# SPI_IFC.net
KiCad netlist of a schematic drawn in Altium Designer
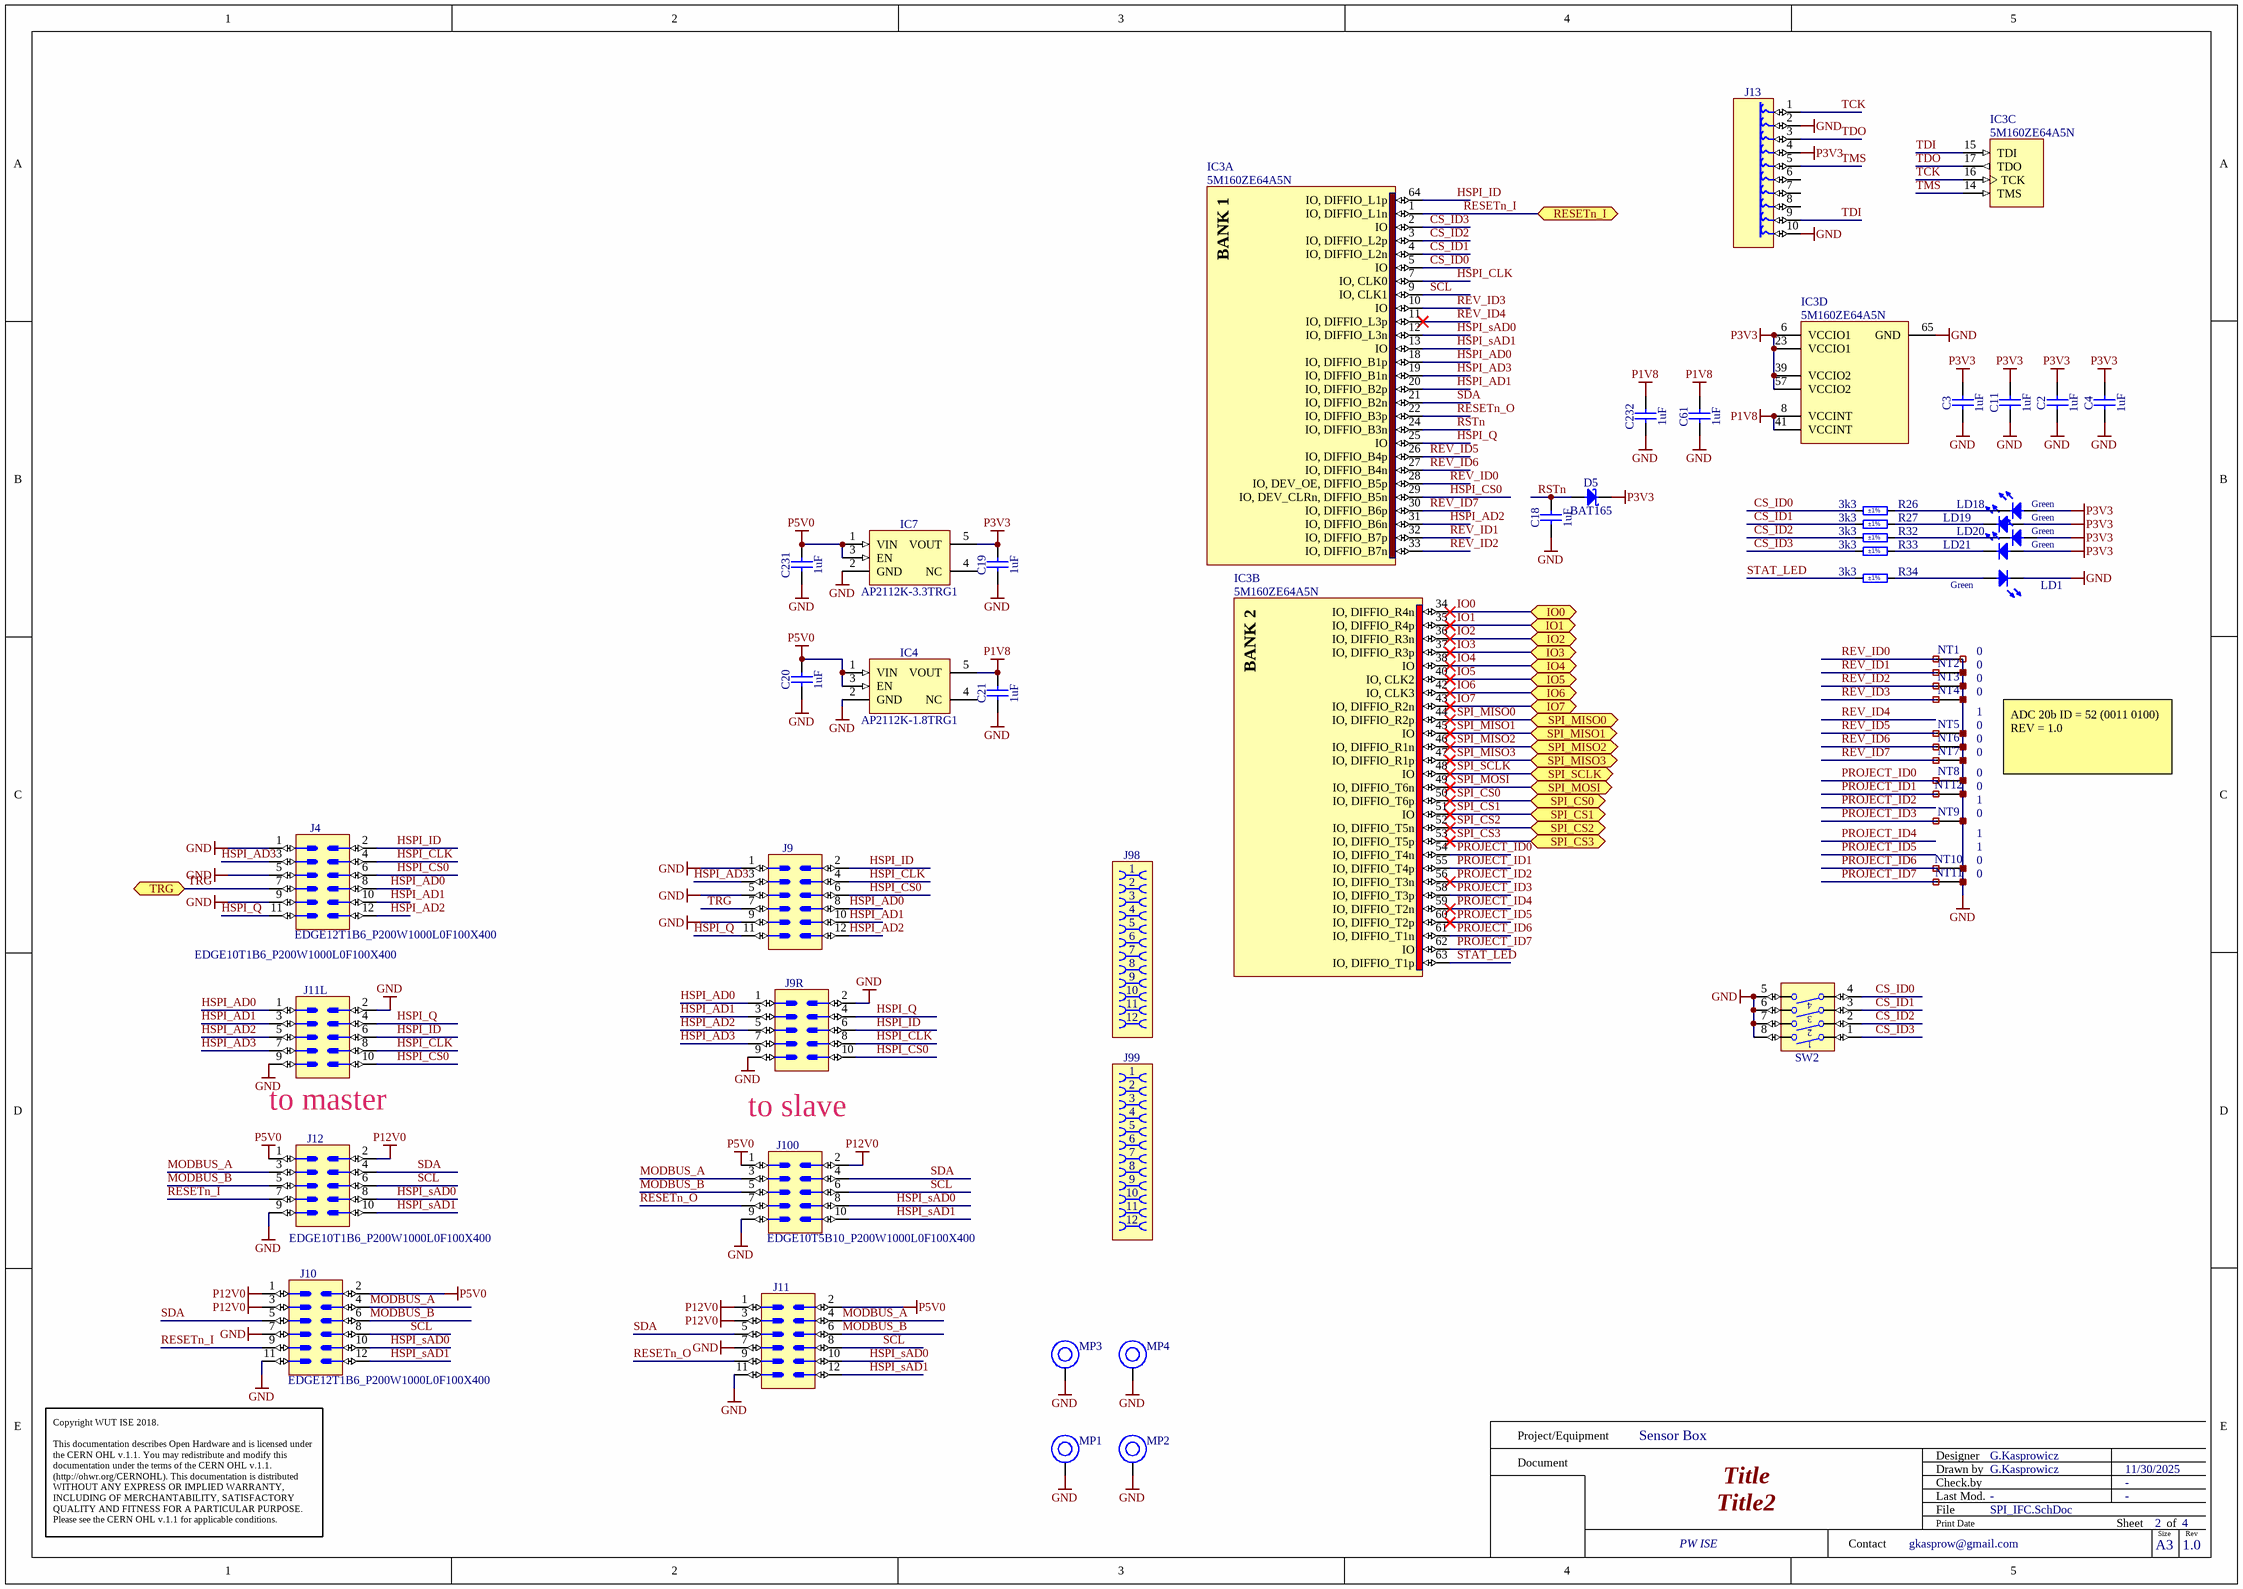
[diagram p0: SPI_IFC.SchDoc]

(export (version "E")
  (design (tool "Eeschema 10.0.6"))
  (components
    (comp (ref "C2")
      (value "1uF")
      (footprint "CAPC1005X55N")
      (description "Non-polarised capacitor")
      (fields
        (field (name "PART NUMBER") "CC0402_1UF_16V_10%_X5R")
        (field (name "VOLTAGE") "16V")
        (field (name "AUTHOR") "CERN DEM JLC")
      )
      (libsource (lib "Capacitors") (part "Capacitor - non polarized"))
    )
    (comp (ref "C3")
      (value "1uF")
      (footprint "CAPC1005X55N")
      (description "Non-polarised capacitor")
      (fields
        (field (name "PART NUMBER") "CC0402_1UF_16V_10%_X5R")
        (field (name "VOLTAGE") "16V")
        (field (name "AUTHOR") "CERN DEM JLC")
      )
      (libsource (lib "Capacitors") (part "Capacitor - non polarized"))
    )
    (comp (ref "C4")
      (value "1uF")
      (footprint "CAPC1005X55N")
      (description "Non-polarised capacitor")
      (fields
        (field (name "PART NUMBER") "CC0402_1UF_16V_10%_X5R")
        (field (name "VOLTAGE") "16V")
        (field (name "AUTHOR") "CERN DEM JLC")
      )
      (libsource (lib "Capacitors") (part "Capacitor - non polarized"))
    )
    (comp (ref "C11")
      (value "1uF")
      (footprint "CAPC1005X55N")
      (description "Non-polarised capacitor")
      (fields
        (field (name "PART NUMBER") "CC0402_1UF_16V_10%_X5R")
        (field (name "VOLTAGE") "16V")
        (field (name "AUTHOR") "CERN DEM JLC")
      )
      (libsource (lib "Capacitors") (part "Capacitor - non polarized"))
    )
    (comp (ref "C18")
      (value "1uF")
      (footprint "CAPC1005X55N")
      (description "Non-polarised capacitor")
      (fields
        (field (name "PART NUMBER") "CC0402_1UF_16V_10%_X5R")
        (field (name "VOLTAGE") "16V")
        (field (name "AUTHOR") "CERN DEM JLC")
      )
      (libsource (lib "Capacitors") (part "Capacitor - non polarized"))
    )
    (comp (ref "C19")
      (value "1uF")
      (footprint "CAPC1005X55N")
      (description "Non-polarised capacitor")
      (fields
        (field (name "PART NUMBER") "CC0402_1UF_16V_10%_X5R")
        (field (name "VOLTAGE") "16V")
        (field (name "AUTHOR") "CERN DEM JLC")
      )
      (libsource (lib "Capacitors") (part "Capacitor - non polarized"))
    )
    (comp (ref "C20")
      (value "1uF")
      (footprint "CAPC1005X55N")
      (description "Non-polarised capacitor")
      (fields
        (field (name "PART NUMBER") "CC0402_1UF_16V_10%_X5R")
        (field (name "VOLTAGE") "16V")
        (field (name "AUTHOR") "CERN DEM JLC")
      )
      (libsource (lib "Capacitors") (part "Capacitor - non polarized"))
    )
    (comp (ref "C21")
      (value "1uF")
      (footprint "CAPC1005X55N")
      (description "Non-polarised capacitor")
      (fields
        (field (name "PART NUMBER") "CC0402_1UF_16V_10%_X5R")
        (field (name "VOLTAGE") "16V")
        (field (name "AUTHOR") "CERN DEM JLC")
      )
      (libsource (lib "Capacitors") (part "Capacitor - non polarized"))
    )
    (comp (ref "C61")
      (value "1uF")
      (footprint "CAPC1005X55N")
      (description "Non-polarised capacitor")
      (fields
        (field (name "PART NUMBER") "CC0402_1UF_16V_10%_X5R")
        (field (name "VOLTAGE") "16V")
        (field (name "AUTHOR") "CERN DEM JLC")
      )
      (libsource (lib "Capacitors") (part "Capacitor - non polarized"))
    )
    (comp (ref "C231")
      (value "1uF")
      (footprint "CAPC1005X55N")
      (description "Non-polarised capacitor")
      (fields
        (field (name "PART NUMBER") "CC0402_1UF_16V_10%_X5R")
        (field (name "VOLTAGE") "16V")
        (field (name "AUTHOR") "CERN DEM JLC")
      )
      (libsource (lib "Capacitors") (part "Capacitor - non polarized"))
    )
    (comp (ref "C232")
      (value "1uF")
      (footprint "CAPC1005X55N")
      (description "Non-polarised capacitor")
      (fields
        (field (name "PART NUMBER") "CC0402_1UF_16V_10%_X5R")
        (field (name "VOLTAGE") "16V")
        (field (name "AUTHOR") "CERN DEM JLC")
      )
      (libsource (lib "Capacitors") (part "Capacitor - non polarized"))
    )
    (comp (ref "D5")
      (value "BAT165")
      (footprint "SOD2512X110N")
      (description "Schottky Diode")
      (fields
        (field (name "VOLTAGE") "40V")
        (field (name "POWER") "750mA")
        (field (name "AUTHOR") "CERN DEM JLC")
      )
      (libsource (lib "ICs And Semiconductors") (part "Diode Schottky"))
    )
    (comp (ref "IC3")
      (value "5M160ZE64A5N")
      (footprint "QFP40P900X900X120-65N-S550")
      (fields (field (name "MANUFACTURER") "ALTERA") (field (name "AUTHOR") "CERN DEM JLC"))
      (libsource (lib "ICs And Semiconductors") (part "5M160ZE64A5N"))
    )
    (comp (ref "IC4")
      (value "AP2112K-1.8TRG1")
      (footprint "SOT95P285X140-5N")
      (description "600mA CMOS Low Dropout Linear Regulator with Enable")
      (fields
        (field (name "MANUFACTURER") "DIODES INCORPORATED")
        (field (name "MANUFACTURER PART NUMBER") "AP2112K-1.8")
        (field (name "AUTHOR") "CERN DEM JLC")
      )
      (libsource (lib "ICs And Semiconductors") (part "AP2112K"))
    )
    (comp (ref "IC7")
      (value "AP2112K-3.3TRG1")
      (footprint "SOT95P285X140-5N")
      (description "600mA CMOS Low Dropout Linear Regulator with Enable")
      (fields
        (field (name "MANUFACTURER") "DIODES INCORPORATED")
        (field (name "MANUFACTURER PART NUMBER") "AP2112K-3.3")
        (field (name "AUTHOR") "CERN DEM MR")
      )
      (libsource (lib "ICs And Semiconductors") (part "AP2112K"))
    )
    (comp (ref "J4")
      (value "~")
      (footprint "EDGE12T1B6_P200W1000L0F100X400")
      (description "PCB Edge Connector 12 (2x6)")
      (fields
        (field (name "PART NUMBER") "EDGE10T1B6_P200W1000L0F100X400")
        (field (name "AUTHOR") "CERN DEM MR")
      )
      (libsource (lib "Connectors") (part "PCB Edge Connector 12 (2x6)"))
    )
    (comp (ref "J9")
      (value "~")
      (footprint "EDGE12T5B10_P200W1000L0F100X400")
      (description "PCB Edge Connector 12 (2x6)")
      (fields (field (name "PART NUMBER") "EDGE12T5B10_P200W1000L0F100X400") (field (name "AUTHOR") "GK"))
      (libsource (lib "Connectors") (part "PCB Edge Connector 12 (2x6) R"))
    )
    (comp (ref "J9R")
      (value "~")
      (footprint "EDGE10T5B10_P200W1000L0F100X400")
      (description "PCB Edge Connector 10 (2x5)")
      (fields
        (field (name "PART NUMBER") "EDGE10T5B10_P200W1000L0F100X400")
        (field (name "AUTHOR") "CERN DEM MR")
      )
      (libsource (lib "Connectors") (part "PCB Edge Connector 10 (2x5)"))
    )
    (comp (ref "J10")
      (value "~")
      (footprint "EDGE12T1B6_P200W1000L0F100X400")
      (description "PCB Edge Connector 12 (2x6)")
      (fields
        (field (name "PART NUMBER") "EDGE10T1B6_P200W1000L0F100X400")
        (field (name "AUTHOR") "CERN DEM MR")
      )
      (libsource (lib "Connectors") (part "PCB Edge Connector 12 (2x6)"))
    )
    (comp (ref "J11")
      (value "~")
      (footprint "EDGE12T5B10_P200W1000L0F100X400")
      (description "PCB Edge Connector 12 (2x6)")
      (fields (field (name "PART NUMBER") "EDGE12T5B10_P200W1000L0F100X400") (field (name "AUTHOR") "GK"))
      (libsource (lib "Connectors") (part "PCB Edge Connector 12 (2x6) R"))
    )
    (comp (ref "J11L")
      (value "~")
      (footprint "EDGE10T1B6_P200W1000L0F100X400")
      (description "PCB Edge Connector 10 (2x5)")
      (fields
        (field (name "PART NUMBER") "EDGE10T1B6_P200W1000L0F100X400")
        (field (name "AUTHOR") "CERN DEM MR")
      )
      (libsource (lib "Connectors") (part "PCB Edge Connector 10 (2x5)"))
    )
    (comp (ref "J12")
      (value "~")
      (footprint "EDGE10T1B6_P200W1000L0F100X400")
      (description "PCB Edge Connector 10 (2x5)")
      (fields
        (field (name "PART NUMBER") "EDGE10T1B6_P200W1000L0F100X400")
        (field (name "AUTHOR") "CERN DEM MR")
      )
      (libsource (lib "Connectors") (part "PCB Edge Connector 10 (2x5)"))
    )
    (comp (ref "J13")
      (value "TC2050-IDC")
      (footprint "TC2050-IDC")
      (description "TC2030-MCP and TC2050-IDC Pad Contact")
      (fields (field (name "AUTHOR") "CERN DEM HF"))
      (libsource (lib "Eletro-mechanical") (part "TC2050-IDC"))
    )
    (comp (ref "J98")
      (value "~")
      (footprint "AVX_009159012761916")
      (description "Open Ended Card Edge Connector, 9159 Series")
      (fields
        (field (name "PART NUMBER") "AVX_0009159012761916")
        (field (name "MANUFACTURER") "AVX")
        (field (name "AUTHOR") "GK")
      )
      (libsource (lib "Connectors") (part "AVX_009159012761916"))
    )
    (comp (ref "J99")
      (value "~")
      (footprint "AVX_009159012761916")
      (description "Open Ended Card Edge Connector, 9159 Series")
      (fields
        (field (name "PART NUMBER") "AVX_0009159012761916")
        (field (name "MANUFACTURER") "AVX")
        (field (name "AUTHOR") "GK")
      )
      (libsource (lib "Connectors") (part "AVX_009159012761916"))
    )
    (comp (ref "J100")
      (value "~")
      (footprint "EDGE10T5B10_P200W1000L0F100X400")
      (description "PCB Edge Connector 10 (2x5)")
      (fields
        (field (name "PART NUMBER") "EDGE10T5B10_P200W1000L0F100X400")
        (field (name "AUTHOR") "CERN DEM MR")
      )
      (libsource (lib "Connectors") (part "PCB Edge Connector 10 (2x5)"))
    )
    (comp (ref "LD1")
      (value "Green")
      (footprint "LED_KINGBRIGHT_KP-1608CGCK")
      (description "LED Green 1C 2A")
      (fields
        (field (name "PART NUMBER") "LED_KINGBRIGHT_KP-1608CGCK")
        (field (name "MANUFACTURER") "KINGBRIGHT")
        (field (name "AUTHOR") "CERN DEM HF")
      )
      (libsource (lib "ICs And Semiconductors") (part "LED Green 1C 2A"))
    )
    (comp (ref "LD18")
      (value "Green")
      (footprint "LED_KINGBRIGHT_KP-1608CGCK")
      (description "LED Green 1C 2A")
      (fields
        (field (name "PART NUMBER") "LED_KINGBRIGHT_KP-1608CGCK")
        (field (name "MANUFACTURER") "KINGBRIGHT")
        (field (name "AUTHOR") "CERN DEM HF")
      )
      (libsource (lib "ICs And Semiconductors") (part "LED Green 1C 2A"))
    )
    (comp (ref "LD19")
      (value "Green")
      (footprint "LED_KINGBRIGHT_KP-1608CGCK")
      (description "LED Green 1C 2A")
      (fields
        (field (name "PART NUMBER") "LED_KINGBRIGHT_KP-1608CGCK")
        (field (name "MANUFACTURER") "KINGBRIGHT")
        (field (name "AUTHOR") "CERN DEM HF")
      )
      (libsource (lib "ICs And Semiconductors") (part "LED Green 1C 2A"))
    )
    (comp (ref "LD20")
      (value "Green")
      (footprint "LED_KINGBRIGHT_KP-1608CGCK")
      (description "LED Green 1C 2A")
      (fields
        (field (name "PART NUMBER") "LED_KINGBRIGHT_KP-1608CGCK")
        (field (name "MANUFACTURER") "KINGBRIGHT")
        (field (name "AUTHOR") "CERN DEM HF")
      )
      (libsource (lib "ICs And Semiconductors") (part "LED Green 1C 2A"))
    )
    (comp (ref "LD21")
      (value "Green")
      (footprint "LED_KINGBRIGHT_KP-1608CGCK")
      (description "LED Green 1C 2A")
      (fields
        (field (name "PART NUMBER") "LED_KINGBRIGHT_KP-1608CGCK")
        (field (name "MANUFACTURER") "KINGBRIGHT")
        (field (name "AUTHOR") "CERN DEM HF")
      )
      (libsource (lib "ICs And Semiconductors") (part "LED Green 1C 2A"))
    )
    (comp (ref "MP1")
      (value "M1.6 x 3mm")
      (footprint "97730306330")
      (description "WA-SMSI SMT Steel Spacer with internal Thread Bottom closed, OD 3.3mm, M1.6 x 3mm")
      (fields
        (field (name "MANUFACTURER PART NUMBER") "97730306330R")
        (field (name "MANUFACTURER") "Wurth Elektronik")
      )
      (libsource (lib "Altium_WA-SMSI (rev22a)") (part "97730306330R"))
    )
    (comp (ref "MP2")
      (value "M1.6 x 3mm")
      (footprint "97730306330")
      (description "WA-SMSI SMT Steel Spacer with internal Thread Bottom closed, OD 3.3mm, M1.6 x 3mm")
      (fields
        (field (name "MANUFACTURER PART NUMBER") "97730306330R")
        (field (name "MANUFACTURER") "Wurth Elektronik")
      )
      (libsource (lib "Altium_WA-SMSI (rev22a)") (part "97730306330R"))
    )
    (comp (ref "MP3")
      (value "M1.6 x 3mm")
      (footprint "97730306330")
      (description "WA-SMSI SMT Steel Spacer with internal Thread Bottom closed, OD 3.3mm, M1.6 x 3mm")
      (fields
        (field (name "MANUFACTURER PART NUMBER") "97730306330R")
        (field (name "MANUFACTURER") "Wurth Elektronik")
      )
      (libsource (lib "Altium_WA-SMSI (rev22a)") (part "97730306330R"))
    )
    (comp (ref "MP4")
      (value "M1.6 x 3mm")
      (footprint "97730306330")
      (description "WA-SMSI SMT Steel Spacer with internal Thread Bottom closed, OD 3.3mm, M1.6 x 3mm")
      (fields
        (field (name "MANUFACTURER PART NUMBER") "97730306330R")
        (field (name "MANUFACTURER") "Wurth Elektronik")
      )
      (libsource (lib "Altium_WA-SMSI (rev22a)") (part "97730306330R"))
    )
    (comp (ref "NT1")
      (value "Net Tie")
      (footprint "Net Tie 3")
      (fields (field (name "PART NUMBER") "Net Tie 3") (field (name "AUTHOR") "CERN DEM HF"))
      (libsource (lib "Eletro-mechanical") (part "Net Tie_a"))
    )
    (comp (ref "NT2")
      (value "Net Tie")
      (footprint "Net Tie 3")
      (fields (field (name "PART NUMBER") "Net Tie 3") (field (name "AUTHOR") "CERN DEM HF"))
      (libsource (lib "Eletro-mechanical") (part "Net Tie_a"))
    )
    (comp (ref "NT3")
      (value "Net Tie")
      (footprint "Net Tie 3")
      (fields (field (name "PART NUMBER") "Net Tie 3") (field (name "AUTHOR") "CERN DEM HF"))
      (libsource (lib "Eletro-mechanical") (part "Net Tie_a"))
    )
    (comp (ref "NT4")
      (value "Net Tie")
      (footprint "Net Tie 3")
      (fields (field (name "PART NUMBER") "Net Tie 3") (field (name "AUTHOR") "CERN DEM HF"))
      (libsource (lib "Eletro-mechanical") (part "Net Tie_a"))
    )
    (comp (ref "NT5")
      (value "Net Tie")
      (footprint "Net Tie 3")
      (fields (field (name "PART NUMBER") "Net Tie 3") (field (name "AUTHOR") "CERN DEM HF"))
      (libsource (lib "Eletro-mechanical") (part "Net Tie_a"))
    )
    (comp (ref "NT6")
      (value "Net Tie")
      (footprint "Net Tie 3")
      (fields (field (name "PART NUMBER") "Net Tie 3") (field (name "AUTHOR") "CERN DEM HF"))
      (libsource (lib "Eletro-mechanical") (part "Net Tie_a"))
    )
    (comp (ref "NT7")
      (value "Net Tie")
      (footprint "Net Tie 3")
      (fields (field (name "PART NUMBER") "Net Tie 3") (field (name "AUTHOR") "CERN DEM HF"))
      (libsource (lib "Eletro-mechanical") (part "Net Tie_a"))
    )
    (comp (ref "NT8")
      (value "Net Tie")
      (footprint "Net Tie 3")
      (fields (field (name "PART NUMBER") "Net Tie 3") (field (name "AUTHOR") "CERN DEM HF"))
      (libsource (lib "Eletro-mechanical") (part "Net Tie_a"))
    )
    (comp (ref "NT9")
      (value "Net Tie")
      (footprint "Net Tie 3")
      (fields (field (name "PART NUMBER") "Net Tie 3") (field (name "AUTHOR") "CERN DEM HF"))
      (libsource (lib "Eletro-mechanical") (part "Net Tie_a"))
    )
    (comp (ref "NT10")
      (value "Net Tie")
      (footprint "Net Tie 3")
      (fields (field (name "PART NUMBER") "Net Tie 3") (field (name "AUTHOR") "CERN DEM HF"))
      (libsource (lib "Eletro-mechanical") (part "Net Tie_a"))
    )
    (comp (ref "NT11")
      (value "Net Tie")
      (footprint "Net Tie 3")
      (fields (field (name "PART NUMBER") "Net Tie 3") (field (name "AUTHOR") "CERN DEM HF"))
      (libsource (lib "Eletro-mechanical") (part "Net Tie_a"))
    )
    (comp (ref "NT12")
      (value "Net Tie")
      (footprint "Net Tie 3")
      (fields (field (name "PART NUMBER") "Net Tie 3") (field (name "AUTHOR") "CERN DEM HF"))
      (libsource (lib "Eletro-mechanical") (part "Net Tie_a"))
    )
    (comp (ref "R26")
      (value "3k3")
      (footprint "RESC1005X40N")
      (description "Resistor - 1%")
      (fields
        (field (name "TOLERANCE") "±1%")
        (field (name "PART NUMBER") "R0402_3K3_1%_0.0625W_100PPM")
        (field (name "POWER") "0.0625W")
        (field (name "AUTHOR") "CERN DEM JLC")
      )
      (libsource (lib "Resistors") (part "Resistor - 1%"))
    )
    (comp (ref "R27")
      (value "3k3")
      (footprint "RESC1005X40N")
      (description "Resistor - 1%")
      (fields
        (field (name "TOLERANCE") "±1%")
        (field (name "PART NUMBER") "R0402_3K3_1%_0.0625W_100PPM")
        (field (name "POWER") "0.0625W")
        (field (name "AUTHOR") "CERN DEM JLC")
      )
      (libsource (lib "Resistors") (part "Resistor - 1%"))
    )
    (comp (ref "R32")
      (value "3k3")
      (footprint "RESC1005X40N")
      (description "Resistor - 1%")
      (fields
        (field (name "TOLERANCE") "±1%")
        (field (name "PART NUMBER") "R0402_3K3_1%_0.0625W_100PPM")
        (field (name "POWER") "0.0625W")
        (field (name "AUTHOR") "CERN DEM JLC")
      )
      (libsource (lib "Resistors") (part "Resistor - 1%"))
    )
    (comp (ref "R33")
      (value "3k3")
      (footprint "RESC1005X40N")
      (description "Resistor - 1%")
      (fields
        (field (name "TOLERANCE") "±1%")
        (field (name "PART NUMBER") "R0402_3K3_1%_0.0625W_100PPM")
        (field (name "POWER") "0.0625W")
        (field (name "AUTHOR") "CERN DEM JLC")
      )
      (libsource (lib "Resistors") (part "Resistor - 1%"))
    )
    (comp (ref "R34")
      (value "3k3")
      (footprint "RESC1005X40N")
      (description "Resistor - 1%")
      (fields
        (field (name "TOLERANCE") "±1%")
        (field (name "PART NUMBER") "R0402_3K3_1%_0.0625W_100PPM")
        (field (name "POWER") "0.0625W")
        (field (name "AUTHOR") "CERN DEM JLC")
      )
      (libsource (lib "Resistors") (part "Resistor - 1%"))
    )
    (comp (ref "SW2")
      (value "Switch")
      (footprint "SW_OMRON_A6H-4102")
      (description "4 Ways SPST DIP Switch")
      (fields
        (field (name "PART NUMBER") "SW_OMRON_A6H-4102")
        (field (name "MANUFACTURER") "OMRON")
        (field (name "AUTHOR") "CERN DEM JLC")
      )
      (libsource (lib "Eletro-mechanical") (part "SW 4x SPST DIP Switch"))
    )
  )
  (nets
    (net (code "1") (name "/CS_ID0") (class "Default")
      (node (ref "IC3") (pin "5") (pinfunction "IO_5") (pintype "bidirectional"))
      (node (ref "R26") (pin "2") (pinfunction "2_2") (pintype "passive"))
      (node (ref "SW2") (pin "4") (pinfunction "4_4") (pintype "bidirectional"))
    )
    (net (code "2") (name "/CS_ID1") (class "Default")
      (node (ref "IC3") (pin "4") (pinfunction "IO,_DIFFIO_L2n_4") (pintype "bidirectional"))
      (node (ref "R27") (pin "2") (pinfunction "2_2") (pintype "passive"))
      (node (ref "SW2") (pin "3") (pinfunction "3_3") (pintype "bidirectional"))
    )
    (net (code "3") (name "/CS_ID2") (class "Default")
      (node (ref "IC3") (pin "3") (pinfunction "IO,_DIFFIO_L2p_3") (pintype "bidirectional"))
      (node (ref "R32") (pin "2") (pinfunction "2_2") (pintype "passive"))
      (node (ref "SW2") (pin "2") (pinfunction "2_2") (pintype "bidirectional"))
    )
    (net (code "4") (name "/CS_ID3") (class "Default")
      (node (ref "IC3") (pin "2") (pinfunction "IO_2") (pintype "bidirectional"))
      (node (ref "R33") (pin "2") (pinfunction "2_2") (pintype "passive"))
      (node (ref "SW2") (pin "1") (pinfunction "1_1") (pintype "bidirectional"))
    )
    (net (code "5") (name "/HSPI_AD0") (class "Default")
      (node (ref "IC3") (pin "18") (pinfunction "IO,_DIFFIO_B1p_18") (pintype "bidirectional"))
      (node (ref "J11L") (pin "1") (pinfunction "1_1") (pintype "bidirectional"))
      (node (ref "J4") (pin "8") (pinfunction "8_8") (pintype "bidirectional"))
      (node (ref "J9") (pin "8") (pinfunction "8_8") (pintype "bidirectional"))
      (node (ref "J9R") (pin "1") (pinfunction "1_1") (pintype "bidirectional"))
    )
    (net (code "6") (name "/HSPI_AD1") (class "Default")
      (node (ref "IC3") (pin "20") (pinfunction "IO,_DIFFIO_B2p_20") (pintype "bidirectional"))
      (node (ref "J11L") (pin "3") (pinfunction "3_3") (pintype "bidirectional"))
      (node (ref "J4") (pin "10") (pinfunction "10_10") (pintype "bidirectional"))
      (node (ref "J9") (pin "10") (pinfunction "10_10") (pintype "bidirectional"))
      (node (ref "J9R") (pin "3") (pinfunction "3_3") (pintype "bidirectional"))
    )
    (net (code "7") (name "/HSPI_AD2") (class "Default")
      (node (ref "IC3") (pin "31") (pinfunction "IO,_DIFFIO_B6n_31") (pintype "bidirectional"))
      (node (ref "J11L") (pin "5") (pinfunction "5_5") (pintype "bidirectional"))
      (node (ref "J4") (pin "12") (pinfunction "12_12") (pintype "bidirectional"))
      (node (ref "J9") (pin "12") (pinfunction "12_12") (pintype "bidirectional"))
      (node (ref "J9R") (pin "5") (pinfunction "5_5") (pintype "bidirectional"))
    )
    (net (code "8") (name "/HSPI_AD3") (class "Default")
      (node (ref "IC3") (pin "19") (pinfunction "IO,_DIFFIO_B1n_19") (pintype "bidirectional"))
      (node (ref "J11L") (pin "7") (pinfunction "7_7") (pintype "bidirectional"))
      (node (ref "J4") (pin "3") (pinfunction "3_3") (pintype "bidirectional"))
      (node (ref "J9") (pin "3") (pinfunction "3_3") (pintype "bidirectional"))
      (node (ref "J9R") (pin "7") (pinfunction "7_7") (pintype "bidirectional"))
    )
    (net (code "9") (name "/HSPI_CLK") (class "Default")
      (node (ref "IC3") (pin "7") (pinfunction "IO,_CLK0_7") (pintype "bidirectional"))
      (node (ref "J11L") (pin "8") (pinfunction "8_8") (pintype "bidirectional"))
      (node (ref "J4") (pin "4") (pinfunction "4_4") (pintype "bidirectional"))
      (node (ref "J9") (pin "4") (pinfunction "4_4") (pintype "bidirectional"))
      (node (ref "J9R") (pin "8") (pinfunction "8_8") (pintype "bidirectional"))
    )
    (net (code "10") (name "/HSPI_CS0") (class "Default")
      (node (ref "IC3") (pin "29") (pinfunction "IO,_DEV_CLRn,_DIFFIO_B5n_29") (pintype "bidirectional"))
      (node (ref "J11L") (pin "10") (pinfunction "10_10") (pintype "bidirectional"))
      (node (ref "J4") (pin "6") (pinfunction "6_6") (pintype "bidirectional"))
      (node (ref "J9") (pin "6") (pinfunction "6_6") (pintype "bidirectional"))
      (node (ref "J9R") (pin "10") (pinfunction "10_10") (pintype "bidirectional"))
    )
    (net (code "11") (name "/HSPI_ID") (class "Default")
      (node (ref "IC3") (pin "64") (pinfunction "IO,_DIFFIO_L1p_64") (pintype "bidirectional"))
      (node (ref "J11L") (pin "6") (pinfunction "6_6") (pintype "bidirectional"))
      (node (ref "J4") (pin "2") (pinfunction "2_2") (pintype "bidirectional"))
      (node (ref "J9") (pin "2") (pinfunction "2_2") (pintype "bidirectional"))
      (node (ref "J9R") (pin "6") (pinfunction "6_6") (pintype "bidirectional"))
    )
    (net (code "12") (name "/HSPI_Q") (class "Default")
      (node (ref "IC3") (pin "25") (pinfunction "IO_25") (pintype "bidirectional"))
      (node (ref "J11L") (pin "4") (pinfunction "4_4") (pintype "bidirectional"))
      (node (ref "J4") (pin "11") (pinfunction "11_11") (pintype "bidirectional"))
      (node (ref "J9") (pin "11") (pinfunction "11_11") (pintype "bidirectional"))
      (node (ref "J9R") (pin "4") (pinfunction "4_4") (pintype "bidirectional"))
    )
    (net (code "13") (name "/HSPI_sAD0") (class "Default")
      (node (ref "IC3") (pin "12") (pinfunction "IO,_DIFFIO_L3n_12") (pintype "bidirectional"))
      (node (ref "J10") (pin "10") (pinfunction "10_10") (pintype "bidirectional"))
      (node (ref "J100") (pin "8") (pinfunction "8_8") (pintype "bidirectional"))
      (node (ref "J11") (pin "10") (pinfunction "10_10") (pintype "bidirectional"))
      (node (ref "J12") (pin "8") (pinfunction "8_8") (pintype "bidirectional"))
    )
    (net (code "14") (name "/HSPI_sAD1") (class "Default")
      (node (ref "IC3") (pin "13") (pinfunction "IO_13") (pintype "bidirectional"))
      (node (ref "J10") (pin "12") (pinfunction "12_12") (pintype "bidirectional"))
      (node (ref "J100") (pin "10") (pinfunction "10_10") (pintype "bidirectional"))
      (node (ref "J11") (pin "12") (pinfunction "12_12") (pintype "bidirectional"))
      (node (ref "J12") (pin "10") (pinfunction "10_10") (pintype "bidirectional"))
    )
    (net (code "15") (name "/IO0") (class "Default")
      (node (ref "IC3") (pin "34") (pinfunction "IO,_DIFFIO_R4n_34") (pintype "bidirectional+no_connect"))
    )
    (net (code "16") (name "/IO1") (class "Default")
      (node (ref "IC3") (pin "35") (pinfunction "IO,_DIFFIO_R4p_35") (pintype "bidirectional+no_connect"))
    )
    (net (code "17") (name "/IO2") (class "Default")
      (node (ref "IC3") (pin "36") (pinfunction "IO,_DIFFIO_R3n_36") (pintype "bidirectional+no_connect"))
    )
    (net (code "18") (name "/IO3") (class "Default")
      (node (ref "IC3") (pin "37") (pinfunction "IO,_DIFFIO_R3p_37") (pintype "bidirectional+no_connect"))
    )
    (net (code "19") (name "/IO4") (class "Default")
      (node (ref "IC3") (pin "38") (pinfunction "IO_38") (pintype "bidirectional+no_connect"))
    )
    (net (code "20") (name "/IO5") (class "Default")
      (node (ref "IC3") (pin "40") (pinfunction "IO,_CLK2_40") (pintype "bidirectional+no_connect"))
    )
    (net (code "21") (name "/IO6") (class "Default")
      (node (ref "IC3") (pin "42") (pinfunction "IO,_CLK3_42") (pintype "bidirectional+no_connect"))
    )
    (net (code "22") (name "/IO7") (class "Default")
      (node (ref "IC3") (pin "43") (pinfunction "IO,_DIFFIO_R2n_43") (pintype "bidirectional+no_connect"))
    )
    (net (code "23") (name "/MODBUS_A") (class "Default")
      (node (ref "J10") (pin "4") (pinfunction "4_4") (pintype "bidirectional"))
      (node (ref "J100") (pin "3") (pinfunction "3_3") (pintype "bidirectional"))
      (node (ref "J11") (pin "4") (pinfunction "4_4") (pintype "bidirectional"))
      (node (ref "J12") (pin "3") (pinfunction "3_3") (pintype "bidirectional"))
    )
    (net (code "24") (name "/MODBUS_B") (class "Default")
      (node (ref "J10") (pin "6") (pinfunction "6_6") (pintype "bidirectional"))
      (node (ref "J100") (pin "5") (pinfunction "5_5") (pintype "bidirectional"))
      (node (ref "J11") (pin "6") (pinfunction "6_6") (pintype "bidirectional"))
      (node (ref "J12") (pin "5") (pinfunction "5_5") (pintype "bidirectional"))
    )
    (net (code "25") (name "/PROJECT_ID0") (class "Default")
      (node (ref "IC3") (pin "54") (pinfunction "IO,_DIFFIO_T4n_54") (pintype "bidirectional"))
      (node (ref "NT8") (pin "1") (pinfunction "1_1") (pintype "bidirectional"))
    )
    (net (code "26") (name "/PROJECT_ID1") (class "Default")
      (node (ref "IC3") (pin "55") (pinfunction "IO,_DIFFIO_T4p_55") (pintype "bidirectional"))
      (node (ref "NT12") (pin "1") (pinfunction "1_1") (pintype "bidirectional"))
    )
    (net (code "27") (name "/PROJECT_ID2") (class "Default")
      (node (ref "IC3") (pin "56") (pinfunction "IO,_DIFFIO_T3n_56") (pintype "bidirectional+no_connect"))
    )
    (net (code "28") (name "/PROJECT_ID3") (class "Default")
      (node (ref "IC3") (pin "58") (pinfunction "IO,_DIFFIO_T3p_58") (pintype "bidirectional"))
      (node (ref "NT9") (pin "1") (pinfunction "1_1") (pintype "bidirectional"))
    )
    (net (code "29") (name "/PROJECT_ID4") (class "Default")
      (node (ref "IC3") (pin "59") (pinfunction "IO,_DIFFIO_T2n_59") (pintype "bidirectional+no_connect"))
    )
    (net (code "30") (name "/PROJECT_ID5") (class "Default")
      (node (ref "IC3") (pin "60") (pinfunction "IO,_DIFFIO_T2p_60") (pintype "bidirectional+no_connect"))
    )
    (net (code "31") (name "/PROJECT_ID6") (class "Default")
      (node (ref "IC3") (pin "61") (pinfunction "IO,_DIFFIO_T1n_61") (pintype "bidirectional"))
      (node (ref "NT10") (pin "1") (pinfunction "1_1") (pintype "bidirectional"))
    )
    (net (code "32") (name "/PROJECT_ID7") (class "Default")
      (node (ref "IC3") (pin "62") (pinfunction "IO_62") (pintype "bidirectional"))
      (node (ref "NT11") (pin "1") (pinfunction "1_1") (pintype "bidirectional"))
    )
    (net (code "33") (name "/RESETn_I") (class "Default")
      (node (ref "IC3") (pin "1") (pinfunction "IO,_DIFFIO_L1n_1") (pintype "bidirectional"))
      (node (ref "J10") (pin "9") (pinfunction "9_9") (pintype "bidirectional"))
      (node (ref "J12") (pin "7") (pinfunction "7_7") (pintype "bidirectional"))
    )
    (net (code "34") (name "/RESETn_O") (class "Default")
      (node (ref "IC3") (pin "22") (pinfunction "IO,_DIFFIO_B3p_22") (pintype "bidirectional"))
      (node (ref "J100") (pin "7") (pinfunction "7_7") (pintype "bidirectional"))
      (node (ref "J11") (pin "9") (pinfunction "9_9") (pintype "bidirectional"))
    )
    (net (code "35") (name "/REV_ID0") (class "Default")
      (node (ref "IC3") (pin "28") (pinfunction "IO,_DEV_OE,_DIFFIO_B5p_28") (pintype "bidirectional"))
      (node (ref "NT1") (pin "1") (pinfunction "1_1") (pintype "bidirectional"))
    )
    (net (code "36") (name "/REV_ID1") (class "Default")
      (node (ref "IC3") (pin "32") (pinfunction "IO,_DIFFIO_B7p_32") (pintype "bidirectional"))
      (node (ref "NT2") (pin "1") (pinfunction "1_1") (pintype "bidirectional"))
    )
    (net (code "37") (name "/REV_ID2") (class "Default")
      (node (ref "IC3") (pin "33") (pinfunction "IO,_DIFFIO_B7n_33") (pintype "bidirectional"))
      (node (ref "NT3") (pin "1") (pinfunction "1_1") (pintype "bidirectional"))
    )
    (net (code "38") (name "/REV_ID3") (class "Default")
      (node (ref "IC3") (pin "10") (pinfunction "IO_10") (pintype "bidirectional"))
      (node (ref "NT4") (pin "1") (pinfunction "1_1") (pintype "bidirectional"))
    )
    (net (code "39") (name "/REV_ID4") (class "Default")
      (node (ref "IC3") (pin "11") (pinfunction "IO,_DIFFIO_L3p_11") (pintype "bidirectional+no_connect"))
    )
    (net (code "40") (name "/REV_ID5") (class "Default")
      (node (ref "IC3") (pin "26") (pinfunction "IO,_DIFFIO_B4p_26") (pintype "bidirectional"))
      (node (ref "NT5") (pin "1") (pinfunction "1_1") (pintype "bidirectional"))
    )
    (net (code "41") (name "/REV_ID6") (class "Default")
      (node (ref "IC3") (pin "27") (pinfunction "IO,_DIFFIO_B4n_27") (pintype "bidirectional"))
      (node (ref "NT6") (pin "1") (pinfunction "1_1") (pintype "bidirectional"))
    )
    (net (code "42") (name "/REV_ID7") (class "Default")
      (node (ref "IC3") (pin "30") (pinfunction "IO,_DIFFIO_B6p_30") (pintype "bidirectional"))
      (node (ref "NT7") (pin "1") (pinfunction "1_1") (pintype "bidirectional"))
    )
    (net (code "43") (name "/RSTn") (class "Default")
      (node (ref "C18") (pin "2") (pinfunction "2_2") (pintype "passive"))
      (node (ref "D5") (pin "2") (pinfunction "A_2") (pintype "passive"))
      (node (ref "IC3") (pin "24") (pinfunction "IO,_DIFFIO_B3n_24") (pintype "bidirectional"))
    )
    (net (code "44") (name "/SCL") (class "Default")
      (node (ref "IC3") (pin "9") (pinfunction "IO,_CLK1_9") (pintype "bidirectional"))
      (node (ref "J10") (pin "8") (pinfunction "8_8") (pintype "bidirectional"))
      (node (ref "J100") (pin "6") (pinfunction "6_6") (pintype "bidirectional"))
      (node (ref "J11") (pin "8") (pinfunction "8_8") (pintype "bidirectional"))
      (node (ref "J12") (pin "6") (pinfunction "6_6") (pintype "bidirectional"))
    )
    (net (code "45") (name "/SDA") (class "Default")
      (node (ref "IC3") (pin "21") (pinfunction "IO,_DIFFIO_B2n_21") (pintype "bidirectional"))
      (node (ref "J10") (pin "5") (pinfunction "5_5") (pintype "bidirectional"))
      (node (ref "J100") (pin "4") (pinfunction "4_4") (pintype "bidirectional"))
      (node (ref "J11") (pin "5") (pinfunction "5_5") (pintype "bidirectional"))
      (node (ref "J12") (pin "4") (pinfunction "4_4") (pintype "bidirectional"))
    )
    (net (code "46") (name "/SPI_CS0") (class "Default")
      (node (ref "IC3") (pin "50") (pinfunction "IO,_DIFFIO_T6p_50") (pintype "bidirectional+no_connect"))
    )
    (net (code "47") (name "/SPI_CS1") (class "Default")
      (node (ref "IC3") (pin "51") (pinfunction "IO_51") (pintype "bidirectional+no_connect"))
    )
    (net (code "48") (name "/SPI_CS2") (class "Default")
      (node (ref "IC3") (pin "52") (pinfunction "IO,_DIFFIO_T5n_52") (pintype "bidirectional+no_connect"))
    )
    (net (code "49") (name "/SPI_CS3") (class "Default")
      (node (ref "IC3") (pin "53") (pinfunction "IO,_DIFFIO_T5p_53") (pintype "bidirectional+no_connect"))
    )
    (net (code "50") (name "/SPI_MISO0") (class "Default")
      (node (ref "IC3") (pin "44") (pinfunction "IO,_DIFFIO_R2p_44") (pintype "bidirectional+no_connect"))
    )
    (net (code "51") (name "/SPI_MISO1") (class "Default")
      (node (ref "IC3") (pin "45") (pinfunction "IO_45") (pintype "bidirectional+no_connect"))
    )
    (net (code "52") (name "/SPI_MISO2") (class "Default")
      (node (ref "IC3") (pin "46") (pinfunction "IO,_DIFFIO_R1n_46") (pintype "bidirectional+no_connect"))
    )
    (net (code "53") (name "/SPI_MISO3") (class "Default")
      (node (ref "IC3") (pin "47") (pinfunction "IO,_DIFFIO_R1p_47") (pintype "bidirectional+no_connect"))
    )
    (net (code "54") (name "/SPI_MOSI") (class "Default")
      (node (ref "IC3") (pin "49") (pinfunction "IO,_DIFFIO_T6n_49") (pintype "bidirectional+no_connect"))
    )
    (net (code "55") (name "/SPI_SCLK") (class "Default")
      (node (ref "IC3") (pin "48") (pinfunction "IO_48") (pintype "bidirectional+no_connect"))
    )
    (net (code "56") (name "/STAT_LED") (class "Default")
      (node (ref "IC3") (pin "63") (pinfunction "IO,_DIFFIO_T1p_63") (pintype "bidirectional"))
      (node (ref "R34") (pin "2") (pinfunction "2_2") (pintype "passive"))
    )
    (net (code "57") (name "/TCK") (class "Default")
      (node (ref "IC3") (pin "16") (pinfunction "TCK_16") (pintype "input"))
      (node (ref "J13") (pin "1") (pinfunction "1_1") (pintype "bidirectional"))
    )
    (net (code "58") (name "/TDI") (class "Default")
      (node (ref "IC3") (pin "15") (pinfunction "TDI_15") (pintype "input"))
      (node (ref "J13") (pin "9") (pinfunction "9_9") (pintype "bidirectional"))
    )
    (net (code "59") (name "/TDO") (class "Default")
      (node (ref "IC3") (pin "17") (pinfunction "TDO_17") (pintype "output"))
      (node (ref "J13") (pin "3") (pinfunction "3_3") (pintype "bidirectional"))
    )
    (net (code "60") (name "/TMS") (class "Default")
      (node (ref "IC3") (pin "14") (pinfunction "TMS_14") (pintype "input"))
      (node (ref "J13") (pin "5") (pinfunction "5_5") (pintype "bidirectional"))
    )
    (net (code "61") (name "/TRG") (class "Default")
      (node (ref "J4") (pin "7") (pinfunction "7_7") (pintype "bidirectional"))
      (node (ref "J9") (pin "7") (pinfunction "7_7") (pintype "bidirectional"))
    )
    (net (code "62") (name "GND") (class "Default")
      (node (ref "C11") (pin "1") (pinfunction "1_1") (pintype "passive"))
      (node (ref "C18") (pin "1") (pinfunction "1_1") (pintype "passive"))
      (node (ref "C19") (pin "1") (pinfunction "1_1") (pintype "passive"))
      (node (ref "C2") (pin "1") (pinfunction "1_1") (pintype "passive"))
      (node (ref "C20") (pin "1") (pinfunction "1_1") (pintype "passive"))
      (node (ref "C21") (pin "1") (pinfunction "1_1") (pintype "passive"))
      (node (ref "C231") (pin "1") (pinfunction "1_1") (pintype "passive"))
      (node (ref "C232") (pin "1") (pinfunction "1_1") (pintype "passive"))
      (node (ref "C3") (pin "1") (pinfunction "1_1") (pintype "passive"))
      (node (ref "C4") (pin "1") (pinfunction "1_1") (pintype "passive"))
      (node (ref "C61") (pin "1") (pinfunction "1_1") (pintype "passive"))
      (node (ref "IC3") (pin "65") (pinfunction "GND_65") (pintype "power_in"))
      (node (ref "IC4") (pin "2") (pinfunction "GND_2") (pintype "power_in"))
      (node (ref "IC7") (pin "2") (pinfunction "GND_2") (pintype "power_in"))
      (node (ref "J10") (pin "11") (pinfunction "11_11") (pintype "bidirectional"))
      (node (ref "J10") (pin "7") (pinfunction "7_7") (pintype "bidirectional"))
      (node (ref "J100") (pin "9") (pinfunction "9_9") (pintype "bidirectional"))
      (node (ref "J11") (pin "11") (pinfunction "11_11") (pintype "bidirectional"))
      (node (ref "J11") (pin "7") (pinfunction "7_7") (pintype "bidirectional"))
      (node (ref "J11L") (pin "2") (pinfunction "2_2") (pintype "bidirectional"))
      (node (ref "J11L") (pin "9") (pinfunction "9_9") (pintype "bidirectional"))
      (node (ref "J12") (pin "9") (pinfunction "9_9") (pintype "bidirectional"))
      (node (ref "J13") (pin "10") (pinfunction "10_10") (pintype "bidirectional"))
      (node (ref "J13") (pin "2") (pinfunction "2_2") (pintype "bidirectional"))
      (node (ref "J4") (pin "1") (pinfunction "1_1") (pintype "bidirectional"))
      (node (ref "J4") (pin "5") (pinfunction "5_5") (pintype "bidirectional"))
      (node (ref "J4") (pin "9") (pinfunction "9_9") (pintype "bidirectional"))
      (node (ref "J9") (pin "1") (pinfunction "1_1") (pintype "bidirectional"))
      (node (ref "J9") (pin "5") (pinfunction "5_5") (pintype "bidirectional"))
      (node (ref "J9") (pin "9") (pinfunction "9_9") (pintype "bidirectional"))
      (node (ref "J9R") (pin "2") (pinfunction "2_2") (pintype "bidirectional"))
      (node (ref "J9R") (pin "9") (pinfunction "9_9") (pintype "bidirectional"))
      (node (ref "LD1") (pin "1") (pinfunction "C_1") (pintype "passive"))
      (node (ref "MP1") (pin "1") (pinfunction "1_1") (pintype "passive"))
      (node (ref "MP2") (pin "1") (pinfunction "1_1") (pintype "passive"))
      (node (ref "MP3") (pin "1") (pinfunction "1_1") (pintype "passive"))
      (node (ref "MP4") (pin "1") (pinfunction "1_1") (pintype "passive"))
      (node (ref "NT1") (pin "2") (pinfunction "2_2") (pintype "bidirectional"))
      (node (ref "NT10") (pin "2") (pinfunction "2_2") (pintype "bidirectional"))
      (node (ref "NT11") (pin "2") (pinfunction "2_2") (pintype "bidirectional"))
      (node (ref "NT12") (pin "2") (pinfunction "2_2") (pintype "bidirectional"))
      (node (ref "NT2") (pin "2") (pinfunction "2_2") (pintype "bidirectional"))
      (node (ref "NT3") (pin "2") (pinfunction "2_2") (pintype "bidirectional"))
      (node (ref "NT4") (pin "2") (pinfunction "2_2") (pintype "bidirectional"))
      (node (ref "NT5") (pin "2") (pinfunction "2_2") (pintype "bidirectional"))
      (node (ref "NT6") (pin "2") (pinfunction "2_2") (pintype "bidirectional"))
      (node (ref "NT7") (pin "2") (pinfunction "2_2") (pintype "bidirectional"))
      (node (ref "NT8") (pin "2") (pinfunction "2_2") (pintype "bidirectional"))
      (node (ref "NT9") (pin "2") (pinfunction "2_2") (pintype "bidirectional"))
      (node (ref "SW2") (pin "5") (pinfunction "5_5") (pintype "bidirectional"))
      (node (ref "SW2") (pin "6") (pinfunction "6_6") (pintype "bidirectional"))
      (node (ref "SW2") (pin "7") (pinfunction "7_7") (pintype "bidirectional"))
      (node (ref "SW2") (pin "8") (pinfunction "8_8") (pintype "bidirectional"))
    )
    (net (code "63") (name "Net-(LD1-A)") (class "Default")
      (node (ref "LD1") (pin "2") (pinfunction "A_2") (pintype "passive"))
      (node (ref "R34") (pin "1") (pinfunction "1_1") (pintype "passive"))
    )
    (net (code "64") (name "Net-(LD18-C)") (class "Default")
      (node (ref "LD18") (pin "1") (pinfunction "C_1") (pintype "passive"))
      (node (ref "R26") (pin "1") (pinfunction "1_1") (pintype "passive"))
    )
    (net (code "65") (name "Net-(LD19-C)") (class "Default")
      (node (ref "LD19") (pin "1") (pinfunction "C_1") (pintype "passive"))
      (node (ref "R27") (pin "1") (pinfunction "1_1") (pintype "passive"))
    )
    (net (code "66") (name "Net-(LD20-C)") (class "Default")
      (node (ref "LD20") (pin "1") (pinfunction "C_1") (pintype "passive"))
      (node (ref "R32") (pin "1") (pinfunction "1_1") (pintype "passive"))
    )
    (net (code "67") (name "Net-(LD21-C)") (class "Default")
      (node (ref "LD21") (pin "1") (pinfunction "C_1") (pintype "passive"))
      (node (ref "R33") (pin "1") (pinfunction "1_1") (pintype "passive"))
    )
    (net (code "68") (name "P1V8") (class "Default")
      (node (ref "C21") (pin "2") (pinfunction "2_2") (pintype "passive"))
      (node (ref "C232") (pin "2") (pinfunction "2_2") (pintype "passive"))
      (node (ref "C61") (pin "2") (pinfunction "2_2") (pintype "passive"))
      (node (ref "IC3") (pin "41") (pinfunction "VCCINT_41") (pintype "power_in"))
      (node (ref "IC3") (pin "8") (pinfunction "VCCINT_8") (pintype "power_in"))
      (node (ref "IC4") (pin "5") (pinfunction "VOUT_5") (pintype "power_in"))
    )
    (net (code "69") (name "P3V3") (class "Default")
      (node (ref "C11") (pin "2") (pinfunction "2_2") (pintype "passive"))
      (node (ref "C19") (pin "2") (pinfunction "2_2") (pintype "passive"))
      (node (ref "C2") (pin "2") (pinfunction "2_2") (pintype "passive"))
      (node (ref "C3") (pin "2") (pinfunction "2_2") (pintype "passive"))
      (node (ref "C4") (pin "2") (pinfunction "2_2") (pintype "passive"))
      (node (ref "D5") (pin "1") (pinfunction "C_1") (pintype "passive"))
      (node (ref "IC3") (pin "23") (pinfunction "VCCIO1_23") (pintype "power_in"))
      (node (ref "IC3") (pin "39") (pinfunction "VCCIO2_39") (pintype "power_in"))
      (node (ref "IC3") (pin "57") (pinfunction "VCCIO2_57") (pintype "power_in"))
      (node (ref "IC3") (pin "6") (pinfunction "VCCIO1_6") (pintype "power_in"))
      (node (ref "IC7") (pin "5") (pinfunction "VOUT_5") (pintype "power_in"))
      (node (ref "J13") (pin "4") (pinfunction "4_4") (pintype "bidirectional"))
      (node (ref "LD18") (pin "2") (pinfunction "A_2") (pintype "passive"))
      (node (ref "LD19") (pin "2") (pinfunction "A_2") (pintype "passive"))
      (node (ref "LD20") (pin "2") (pinfunction "A_2") (pintype "passive"))
      (node (ref "LD21") (pin "2") (pinfunction "A_2") (pintype "passive"))
    )
    (net (code "70") (name "P5V0") (class "Default")
      (node (ref "C20") (pin "2") (pinfunction "2_2") (pintype "passive"))
      (node (ref "C231") (pin "2") (pinfunction "2_2") (pintype "passive"))
      (node (ref "IC4") (pin "1") (pinfunction "VIN_1") (pintype "input"))
      (node (ref "IC4") (pin "3") (pinfunction "EN_3") (pintype "input"))
      (node (ref "IC7") (pin "1") (pinfunction "VIN_1") (pintype "input"))
      (node (ref "IC7") (pin "3") (pinfunction "EN_3") (pintype "input"))
      (node (ref "J10") (pin "2") (pinfunction "2_2") (pintype "bidirectional"))
      (node (ref "J100") (pin "1") (pinfunction "1_1") (pintype "bidirectional"))
      (node (ref "J11") (pin "2") (pinfunction "2_2") (pintype "bidirectional"))
      (node (ref "J12") (pin "1") (pinfunction "1_1") (pintype "bidirectional"))
    )
    (net (code "71") (name "P12V0") (class "Default")
      (node (ref "J10") (pin "1") (pinfunction "1_1") (pintype "bidirectional"))
      (node (ref "J10") (pin "3") (pinfunction "3_3") (pintype "bidirectional"))
      (node (ref "J100") (pin "2") (pinfunction "2_2") (pintype "bidirectional"))
      (node (ref "J11") (pin "1") (pinfunction "1_1") (pintype "bidirectional"))
      (node (ref "J11") (pin "3") (pinfunction "3_3") (pintype "bidirectional"))
      (node (ref "J12") (pin "2") (pinfunction "2_2") (pintype "bidirectional"))
    )
    (net (code "72") (name "unconnected-(IC4-NC-Pad4)") (class "Default")
      (node (ref "IC4") (pin "4") (pinfunction "NC_4") (pintype "passive"))
    )
    (net (code "73") (name "unconnected-(IC7-NC-Pad4)") (class "Default")
      (node (ref "IC7") (pin "4") (pinfunction "NC_4") (pintype "passive"))
    )
    (net (code "74") (name "unconnected-(J13-Pad6)") (class "Default")
      (node (ref "J13") (pin "6") (pinfunction "6_6") (pintype "bidirectional"))
    )
    (net (code "75") (name "unconnected-(J13-Pad7)") (class "Default")
      (node (ref "J13") (pin "7") (pinfunction "7_7") (pintype "bidirectional"))
    )
    (net (code "76") (name "unconnected-(J13-Pad8)") (class "Default")
      (node (ref "J13") (pin "8") (pinfunction "8_8") (pintype "bidirectional"))
    )
  )
)
